# pnc3000-interface.net
KiCad netlist of a schematic drawn in EAGLE
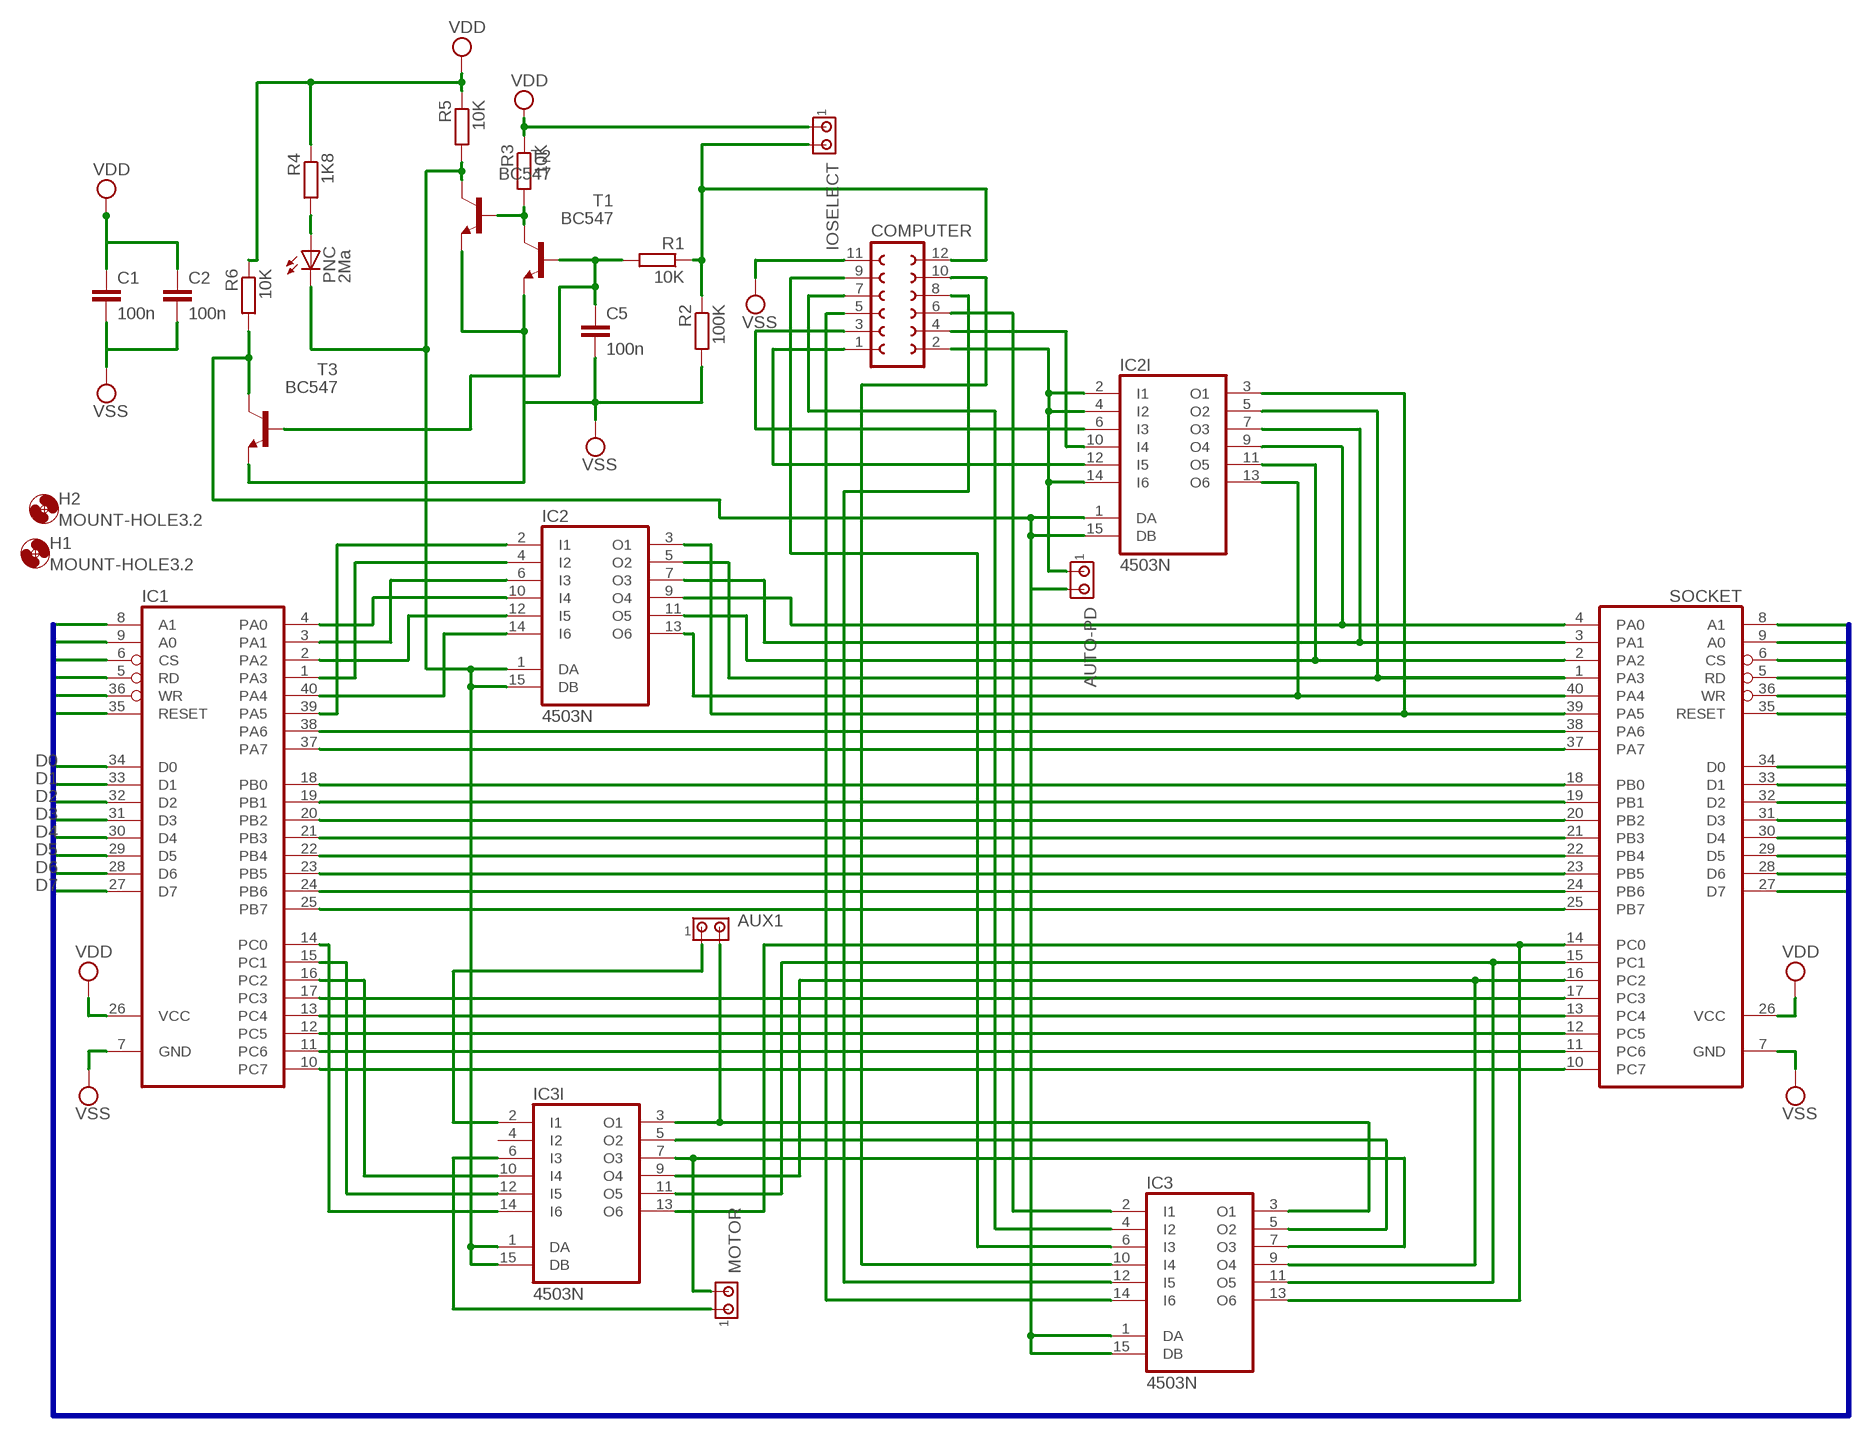
[diagram p0: schematic, sheet 1]

(export (version "E")
  (design (tool "Eeschema 10.0.6"))
  (components
    (comp (ref "AUTO-PD")
      (value "MTA02-100")
      (footprint "eagle-import:10X02MTA")
      (libsource (lib "eagle-import") (part "MTA02-100"))
    )
    (comp (ref "AUX1")
      (value "MTA02-100")
      (footprint "eagle-import:10X02MTA")
      (libsource (lib "eagle-import") (part "MTA02-100"))
    )
    (comp (ref "C1")
      (value "100n")
      (footprint "eagle-import:C050-024X044")
      (libsource (lib "eagle-import") (part "C-EU050-024X044"))
    )
    (comp (ref "C2")
      (value "100n")
      (footprint "eagle-import:C050-024X044")
      (libsource (lib "eagle-import") (part "C-EU050-024X044"))
    )
    (comp (ref "C5")
      (value "100n")
      (footprint "eagle-import:C050-024X044")
      (libsource (lib "eagle-import") (part "C-EU050-024X044"))
    )
    (comp (ref "COMPUTER")
      (value "FE06-2W")
      (footprint "eagle-import:FE06-2W")
      (libsource (lib "eagle-import") (part "FE06-2W"))
    )
    (comp (ref "H1")
      (value "MOUNT-HOLE3.2")
      (footprint "eagle-import:3,2")
      (libsource (lib "eagle-import") (part "MOUNT-HOLE3.2"))
    )
    (comp (ref "H2")
      (value "MOUNT-HOLE3.2")
      (footprint "eagle-import:3,2")
      (libsource (lib "eagle-import") (part "MOUNT-HOLE3.2"))
    )
    (comp (ref "IC1")
      (value "82C55A")
      (footprint "eagle-import:DIL40")
      (fields (field (name "MF") "INTERSIL") (field (name "MPN") "IP82C55AZ"))
      (libsource (lib "eagle-import") (part "82C55A"))
    )
    (comp (ref "IC2")
      (value "4503N")
      (footprint "eagle-import:DIL16")
      (libsource (lib "eagle-import") (part "4503N"))
    )
    (comp (ref "IC2I")
      (value "4503N")
      (footprint "eagle-import:DIL16")
      (libsource (lib "eagle-import") (part "4503N"))
    )
    (comp (ref "IC3")
      (value "4503N")
      (footprint "eagle-import:DIL16")
      (libsource (lib "eagle-import") (part "4503N"))
    )
    (comp (ref "IC3I")
      (value "4503N")
      (footprint "eagle-import:DIL16")
      (libsource (lib "eagle-import") (part "4503N"))
    )
    (comp (ref "IOSELECT")
      (value "MTA02-100")
      (footprint "eagle-import:10X02MTA")
      (libsource (lib "eagle-import") (part "MTA02-100"))
    )
    (comp (ref "MOTOR")
      (value "MTA02-100")
      (footprint "eagle-import:10X02MTA")
      (libsource (lib "eagle-import") (part "MTA02-100"))
    )
    (comp (ref "PNC")
      (value "2Ma")
      (footprint "eagle-import:LED5MM")
      (libsource (lib "eagle-import") (part "LED5MM"))
    )
    (comp (ref "R1")
      (value "10K")
      (footprint "eagle-import:0207_10")
      (libsource (lib "eagle-import") (part "R-EU_0207/10"))
    )
    (comp (ref "R2")
      (value "100K")
      (footprint "eagle-import:0207_10")
      (libsource (lib "eagle-import") (part "R-EU_0207/10"))
    )
    (comp (ref "R3")
      (value "10K")
      (footprint "eagle-import:0207_10")
      (libsource (lib "eagle-import") (part "R-EU_0207/10"))
    )
    (comp (ref "R4")
      (value "1K8")
      (footprint "eagle-import:0207_10")
      (libsource (lib "eagle-import") (part "R-EU_0207/10"))
    )
    (comp (ref "R5")
      (value "10K")
      (footprint "eagle-import:0207_10")
      (libsource (lib "eagle-import") (part "R-EU_0207/10"))
    )
    (comp (ref "R6")
      (value "10K")
      (footprint "eagle-import:0207_10")
      (libsource (lib "eagle-import") (part "R-EU_0207/10"))
    )
    (comp (ref "SOCKET")
      (value "82C55A")
      (footprint "eagle-import:DIL40")
      (fields (field (name "MF") "INTERSIL") (field (name "MPN") "IP82C55AZ"))
      (libsource (lib "eagle-import") (part "82C55A"))
    )
    (comp (ref "T1")
      (value "BC547")
      (footprint "eagle-import:TO92")
      (libsource (lib "eagle-import") (part "BC547"))
    )
    (comp (ref "T2")
      (value "BC547")
      (footprint "eagle-import:TO92")
      (libsource (lib "eagle-import") (part "BC547"))
    )
    (comp (ref "T3")
      (value "BC547")
      (footprint "eagle-import:TO92")
      (libsource (lib "eagle-import") (part "BC547"))
    )
  )
  (nets
    (net (code "1") (name "/A0") (class "Default")
      (node (ref "IC1") (pin "9") (pinfunction "A0_9") (pintype "input"))
      (node (ref "SOCKET") (pin "9") (pinfunction "A0_9") (pintype "input"))
    )
    (net (code "2") (name "/A1") (class "Default")
      (node (ref "IC1") (pin "8") (pinfunction "A1_8") (pintype "input"))
      (node (ref "SOCKET") (pin "8") (pinfunction "A1_8") (pintype "input"))
    )
    (net (code "3") (name "/CS") (class "Default")
      (node (ref "IC1") (pin "6") (pinfunction "CS_6") (pintype "input"))
      (node (ref "SOCKET") (pin "6") (pinfunction "CS_6") (pintype "input"))
    )
    (net (code "4") (name "/D0") (class "Default")
      (node (ref "IC1") (pin "34") (pinfunction "D0_34") (pintype "bidirectional"))
      (node (ref "SOCKET") (pin "34") (pinfunction "D0_34") (pintype "bidirectional"))
    )
    (net (code "5") (name "/D1") (class "Default")
      (node (ref "IC1") (pin "33") (pinfunction "D1_33") (pintype "bidirectional"))
      (node (ref "SOCKET") (pin "33") (pinfunction "D1_33") (pintype "bidirectional"))
    )
    (net (code "6") (name "/D2") (class "Default")
      (node (ref "IC1") (pin "32") (pinfunction "D2_32") (pintype "bidirectional"))
      (node (ref "SOCKET") (pin "32") (pinfunction "D2_32") (pintype "bidirectional"))
    )
    (net (code "7") (name "/D3") (class "Default")
      (node (ref "IC1") (pin "31") (pinfunction "D3_31") (pintype "bidirectional"))
      (node (ref "SOCKET") (pin "31") (pinfunction "D3_31") (pintype "bidirectional"))
    )
    (net (code "8") (name "/D4") (class "Default")
      (node (ref "IC1") (pin "30") (pinfunction "D4_30") (pintype "bidirectional"))
      (node (ref "SOCKET") (pin "30") (pinfunction "D4_30") (pintype "bidirectional"))
    )
    (net (code "9") (name "/D5") (class "Default")
      (node (ref "IC1") (pin "29") (pinfunction "D5_29") (pintype "bidirectional"))
      (node (ref "SOCKET") (pin "29") (pinfunction "D5_29") (pintype "bidirectional"))
    )
    (net (code "10") (name "/D6") (class "Default")
      (node (ref "IC1") (pin "28") (pinfunction "D6_28") (pintype "bidirectional"))
      (node (ref "SOCKET") (pin "28") (pinfunction "D6_28") (pintype "bidirectional"))
    )
    (net (code "11") (name "/D7") (class "Default")
      (node (ref "IC1") (pin "27") (pinfunction "D7_27") (pintype "bidirectional"))
      (node (ref "SOCKET") (pin "27") (pinfunction "D7_27") (pintype "bidirectional"))
    )
    (net (code "12") (name "/RD") (class "Default")
      (node (ref "IC1") (pin "5") (pinfunction "RD_5") (pintype "input"))
      (node (ref "SOCKET") (pin "5") (pinfunction "RD_5") (pintype "input"))
    )
    (net (code "13") (name "/RESET") (class "Default")
      (node (ref "IC1") (pin "35") (pinfunction "RESET_35") (pintype "input"))
      (node (ref "SOCKET") (pin "35") (pinfunction "RESET_35") (pintype "input"))
    )
    (net (code "14") (name "/WR") (class "Default")
      (node (ref "IC1") (pin "36") (pinfunction "WR_36") (pintype "input"))
      (node (ref "SOCKET") (pin "36") (pinfunction "WR_36") (pintype "input"))
    )
    (net (code "15") (name "Net-(COMPUTER-Pad12)") (class "Default")
      (node (ref "COMPUTER") (pin "12") (pinfunction "12_12") (pintype "passive"))
      (node (ref "IOSELECT") (pin "2") (pinfunction "2_2") (pintype "passive"))
      (node (ref "R1") (pin "1") (pinfunction "1_1") (pintype "passive"))
      (node (ref "R2") (pin "1") (pinfunction "1_1") (pintype "passive"))
    )
    (net (code "16") (name "Net-(IC1-PA0)") (class "Default")
      (node (ref "IC1") (pin "4") (pinfunction "PA0_4") (pintype "bidirectional"))
      (node (ref "IC2") (pin "10") (pinfunction "I4_10") (pintype "input"))
    )
    (net (code "17") (name "Net-(IC1-PA1)") (class "Default")
      (node (ref "IC1") (pin "3") (pinfunction "PA1_3") (pintype "bidirectional"))
      (node (ref "IC2") (pin "6") (pinfunction "I3_6") (pintype "input"))
    )
    (net (code "18") (name "Net-(IC1-PA2)") (class "Default")
      (node (ref "IC1") (pin "2") (pinfunction "PA2_2") (pintype "bidirectional"))
      (node (ref "IC2") (pin "12") (pinfunction "I5_12") (pintype "input"))
    )
    (net (code "19") (name "Net-(IC1-PA3)") (class "Default")
      (node (ref "IC1") (pin "1") (pinfunction "PA3_1") (pintype "bidirectional"))
      (node (ref "IC2") (pin "4") (pinfunction "I2_4") (pintype "input"))
    )
    (net (code "20") (name "Net-(IC1-PA4)") (class "Default")
      (node (ref "IC1") (pin "40") (pinfunction "PA4_40") (pintype "bidirectional"))
      (node (ref "IC2") (pin "14") (pinfunction "I6_14") (pintype "input"))
    )
    (net (code "21") (name "Net-(IC1-PA5)") (class "Default")
      (node (ref "IC1") (pin "39") (pinfunction "PA5_39") (pintype "bidirectional"))
      (node (ref "IC2") (pin "2") (pinfunction "I1_2") (pintype "input"))
    )
    (net (code "22") (name "Net-(IC1-PA6)") (class "Default")
      (node (ref "IC1") (pin "38") (pinfunction "PA6_38") (pintype "bidirectional"))
      (node (ref "SOCKET") (pin "38") (pinfunction "PA6_38") (pintype "bidirectional"))
    )
    (net (code "23") (name "Net-(IC1-PA7)") (class "Default")
      (node (ref "IC1") (pin "37") (pinfunction "PA7_37") (pintype "bidirectional"))
      (node (ref "SOCKET") (pin "37") (pinfunction "PA7_37") (pintype "bidirectional"))
    )
    (net (code "24") (name "Net-(IC1-PB0)") (class "Default")
      (node (ref "IC1") (pin "18") (pinfunction "PB0_18") (pintype "bidirectional"))
      (node (ref "SOCKET") (pin "18") (pinfunction "PB0_18") (pintype "bidirectional"))
    )
    (net (code "25") (name "Net-(IC1-PB1)") (class "Default")
      (node (ref "IC1") (pin "19") (pinfunction "PB1_19") (pintype "bidirectional"))
      (node (ref "SOCKET") (pin "19") (pinfunction "PB1_19") (pintype "bidirectional"))
    )
    (net (code "26") (name "Net-(IC1-PB2)") (class "Default")
      (node (ref "IC1") (pin "20") (pinfunction "PB2_20") (pintype "bidirectional"))
      (node (ref "SOCKET") (pin "20") (pinfunction "PB2_20") (pintype "bidirectional"))
    )
    (net (code "27") (name "Net-(IC1-PB3)") (class "Default")
      (node (ref "IC1") (pin "21") (pinfunction "PB3_21") (pintype "bidirectional"))
      (node (ref "SOCKET") (pin "21") (pinfunction "PB3_21") (pintype "bidirectional"))
    )
    (net (code "28") (name "Net-(IC1-PB4)") (class "Default")
      (node (ref "IC1") (pin "22") (pinfunction "PB4_22") (pintype "bidirectional"))
      (node (ref "SOCKET") (pin "22") (pinfunction "PB4_22") (pintype "bidirectional"))
    )
    (net (code "29") (name "Net-(IC1-PB5)") (class "Default")
      (node (ref "IC1") (pin "23") (pinfunction "PB5_23") (pintype "bidirectional"))
      (node (ref "SOCKET") (pin "23") (pinfunction "PB5_23") (pintype "bidirectional"))
    )
    (net (code "30") (name "Net-(IC1-PB6)") (class "Default")
      (node (ref "IC1") (pin "24") (pinfunction "PB6_24") (pintype "bidirectional"))
      (node (ref "SOCKET") (pin "24") (pinfunction "PB6_24") (pintype "bidirectional"))
    )
    (net (code "31") (name "Net-(IC1-PB7)") (class "Default")
      (node (ref "IC1") (pin "25") (pinfunction "PB7_25") (pintype "bidirectional"))
      (node (ref "SOCKET") (pin "25") (pinfunction "PB7_25") (pintype "bidirectional"))
    )
    (net (code "32") (name "Net-(IC1-PC0)") (class "Default")
      (node (ref "IC1") (pin "14") (pinfunction "PC0_14") (pintype "bidirectional"))
      (node (ref "IC3I") (pin "14") (pinfunction "I6_14") (pintype "input"))
    )
    (net (code "33") (name "Net-(IC1-PC1)") (class "Default")
      (node (ref "IC1") (pin "15") (pinfunction "PC1_15") (pintype "bidirectional"))
      (node (ref "IC3I") (pin "12") (pinfunction "I5_12") (pintype "input"))
    )
    (net (code "34") (name "Net-(IC1-PC2)") (class "Default")
      (node (ref "IC1") (pin "16") (pinfunction "PC2_16") (pintype "bidirectional"))
      (node (ref "IC3I") (pin "10") (pinfunction "I4_10") (pintype "input"))
    )
    (net (code "35") (name "Net-(IC1-PC3)") (class "Default")
      (node (ref "IC1") (pin "17") (pinfunction "PC3_17") (pintype "bidirectional"))
      (node (ref "SOCKET") (pin "17") (pinfunction "PC3_17") (pintype "bidirectional"))
    )
    (net (code "36") (name "Net-(IC1-PC4)") (class "Default")
      (node (ref "IC1") (pin "13") (pinfunction "PC4_13") (pintype "bidirectional"))
      (node (ref "SOCKET") (pin "13") (pinfunction "PC4_13") (pintype "bidirectional"))
    )
    (net (code "37") (name "Net-(IC1-PC5)") (class "Default")
      (node (ref "IC1") (pin "12") (pinfunction "PC5_12") (pintype "bidirectional"))
      (node (ref "SOCKET") (pin "12") (pinfunction "PC5_12") (pintype "bidirectional"))
    )
    (net (code "38") (name "Net-(IC1-PC6)") (class "Default")
      (node (ref "IC1") (pin "11") (pinfunction "PC6_11") (pintype "bidirectional"))
      (node (ref "SOCKET") (pin "11") (pinfunction "PC6_11") (pintype "bidirectional"))
    )
    (net (code "39") (name "Net-(IC1-PC7)") (class "Default")
      (node (ref "IC1") (pin "10") (pinfunction "PC7_10") (pintype "bidirectional"))
      (node (ref "SOCKET") (pin "10") (pinfunction "PC7_10") (pintype "bidirectional"))
    )
    (net (code "40") (name "Net-(IC2A-DA)") (class "Default")
      (node (ref "IC2") (pin "1") (pinfunction "DA_1") (pintype "input"))
      (node (ref "IC2") (pin "15") (pinfunction "DB_15") (pintype "input"))
      (node (ref "IC3I") (pin "1") (pinfunction "DA_1") (pintype "input"))
      (node (ref "IC3I") (pin "15") (pinfunction "DB_15") (pintype "input"))
      (node (ref "PNC") (pin "K") (pinfunction "C_K") (pintype "passive"))
      (node (ref "R5") (pin "2") (pinfunction "2_2") (pintype "passive"))
      (node (ref "T2") (pin "3") (pinfunction "C_3") (pintype "passive"))
    )
    (net (code "41") (name "Net-(IC2A-O1)") (class "Default")
      (node (ref "IC2") (pin "3") (pinfunction "O1_3") (pintype "output"))
      (node (ref "IC2I") (pin "3") (pinfunction "O1_3") (pintype "output"))
      (node (ref "SOCKET") (pin "39") (pinfunction "PA5_39") (pintype "bidirectional"))
    )
    (net (code "42") (name "Net-(IC2A-O2)") (class "Default")
      (node (ref "IC2") (pin "5") (pinfunction "O2_5") (pintype "output"))
      (node (ref "IC2I") (pin "5") (pinfunction "O2_5") (pintype "output"))
      (node (ref "SOCKET") (pin "1") (pinfunction "PA3_1") (pintype "bidirectional"))
    )
    (net (code "43") (name "Net-(IC2A-O3)") (class "Default")
      (node (ref "IC2") (pin "7") (pinfunction "O3_7") (pintype "output"))
      (node (ref "IC2I") (pin "7") (pinfunction "O3_7") (pintype "output"))
      (node (ref "SOCKET") (pin "3") (pinfunction "PA1_3") (pintype "bidirectional"))
    )
    (net (code "44") (name "Net-(IC2A-O4)") (class "Default")
      (node (ref "IC2") (pin "9") (pinfunction "O4_9") (pintype "output"))
      (node (ref "IC2I") (pin "9") (pinfunction "O4_9") (pintype "output"))
      (node (ref "SOCKET") (pin "4") (pinfunction "PA0_4") (pintype "bidirectional"))
    )
    (net (code "45") (name "Net-(IC2A-O5)") (class "Default")
      (node (ref "IC2") (pin "11") (pinfunction "O5_11") (pintype "output"))
      (node (ref "IC2I") (pin "11") (pinfunction "O5_11") (pintype "output"))
      (node (ref "SOCKET") (pin "2") (pinfunction "PA2_2") (pintype "bidirectional"))
    )
    (net (code "46") (name "Net-(IC2A-O6)") (class "Default")
      (node (ref "IC2") (pin "13") (pinfunction "O6_13") (pintype "output"))
      (node (ref "IC2I") (pin "13") (pinfunction "O6_13") (pintype "output"))
      (node (ref "SOCKET") (pin "40") (pinfunction "PA4_40") (pintype "bidirectional"))
    )
    (net (code "47") (name "Net-(IC2IA-DA)") (class "Default")
      (node (ref "AUTO-PD") (pin "2") (pinfunction "2_2") (pintype "passive"))
      (node (ref "IC2I") (pin "1") (pinfunction "DA_1") (pintype "input"))
      (node (ref "IC2I") (pin "15") (pinfunction "DB_15") (pintype "input"))
      (node (ref "IC3") (pin "1") (pinfunction "DA_1") (pintype "input"))
      (node (ref "IC3") (pin "15") (pinfunction "DB_15") (pintype "input"))
      (node (ref "R6") (pin "2") (pinfunction "2_2") (pintype "passive"))
      (node (ref "T3") (pin "3") (pinfunction "C_3") (pintype "passive"))
    )
    (net (code "48") (name "Net-(IC2IA-I1)") (class "Default")
      (node (ref "AUTO-PD") (pin "1") (pinfunction "1_1") (pintype "passive"))
      (node (ref "COMPUTER") (pin "2") (pinfunction "2_2") (pintype "passive"))
      (node (ref "IC2I") (pin "14") (pinfunction "I6_14") (pintype "input"))
      (node (ref "IC2I") (pin "2") (pinfunction "I1_2") (pintype "input"))
      (node (ref "IC2I") (pin "4") (pinfunction "I2_4") (pintype "input"))
    )
    (net (code "49") (name "Net-(IC2IA-I3)") (class "Default")
      (node (ref "COMPUTER") (pin "3") (pinfunction "3_3") (pintype "passive"))
      (node (ref "IC2I") (pin "6") (pinfunction "I3_6") (pintype "input"))
    )
    (net (code "50") (name "Net-(IC2IA-I4)") (class "Default")
      (node (ref "COMPUTER") (pin "4") (pinfunction "4_4") (pintype "passive"))
      (node (ref "IC2I") (pin "10") (pinfunction "I4_10") (pintype "input"))
    )
    (net (code "51") (name "Net-(IC2IA-I5)") (class "Default")
      (node (ref "COMPUTER") (pin "1") (pinfunction "1_1") (pintype "passive"))
      (node (ref "IC2I") (pin "12") (pinfunction "I5_12") (pintype "input"))
    )
    (net (code "52") (name "Net-(IC3A-I1)") (class "Default")
      (node (ref "COMPUTER") (pin "6") (pinfunction "6_6") (pintype "passive"))
      (node (ref "IC3") (pin "2") (pinfunction "I1_2") (pintype "input"))
    )
    (net (code "53") (name "Net-(IC3A-I2)") (class "Default")
      (node (ref "COMPUTER") (pin "7") (pinfunction "7_7") (pintype "passive"))
      (node (ref "IC3") (pin "4") (pinfunction "I2_4") (pintype "input"))
    )
    (net (code "54") (name "Net-(IC3A-I3)") (class "Default")
      (node (ref "COMPUTER") (pin "9") (pinfunction "9_9") (pintype "passive"))
      (node (ref "IC3") (pin "6") (pinfunction "I3_6") (pintype "input"))
    )
    (net (code "55") (name "Net-(IC3A-I4)") (class "Default")
      (node (ref "COMPUTER") (pin "10") (pinfunction "10_10") (pintype "passive"))
      (node (ref "IC3") (pin "10") (pinfunction "I4_10") (pintype "input"))
    )
    (net (code "56") (name "Net-(IC3A-I5)") (class "Default")
      (node (ref "COMPUTER") (pin "8") (pinfunction "8_8") (pintype "passive"))
      (node (ref "IC3") (pin "12") (pinfunction "I5_12") (pintype "input"))
    )
    (net (code "57") (name "Net-(IC3A-I6)") (class "Default")
      (node (ref "COMPUTER") (pin "5") (pinfunction "5_5") (pintype "passive"))
      (node (ref "IC3") (pin "14") (pinfunction "I6_14") (pintype "input"))
    )
    (net (code "58") (name "Net-(IC3A-O1)") (class "Default")
      (node (ref "AUX1") (pin "2") (pinfunction "2_2") (pintype "passive"))
      (node (ref "IC3") (pin "3") (pinfunction "O1_3") (pintype "output"))
      (node (ref "IC3I") (pin "3") (pinfunction "O1_3") (pintype "output"))
    )
    (net (code "59") (name "Net-(IC3A-O2)") (class "Default")
      (node (ref "IC3") (pin "5") (pinfunction "O2_5") (pintype "output"))
      (node (ref "IC3I") (pin "5") (pinfunction "O2_5") (pintype "output"))
    )
    (net (code "60") (name "Net-(IC3A-O3)") (class "Default")
      (node (ref "IC3") (pin "7") (pinfunction "O3_7") (pintype "output"))
      (node (ref "IC3I") (pin "7") (pinfunction "O3_7") (pintype "output"))
      (node (ref "MOTOR") (pin "2") (pinfunction "2_2") (pintype "passive"))
    )
    (net (code "61") (name "Net-(IC3A-O4)") (class "Default")
      (node (ref "IC3") (pin "9") (pinfunction "O4_9") (pintype "output"))
      (node (ref "IC3I") (pin "9") (pinfunction "O4_9") (pintype "output"))
      (node (ref "SOCKET") (pin "16") (pinfunction "PC2_16") (pintype "bidirectional"))
    )
    (net (code "62") (name "Net-(IC3A-O5)") (class "Default")
      (node (ref "IC3") (pin "11") (pinfunction "O5_11") (pintype "output"))
      (node (ref "IC3I") (pin "11") (pinfunction "O5_11") (pintype "output"))
      (node (ref "SOCKET") (pin "15") (pinfunction "PC1_15") (pintype "bidirectional"))
    )
    (net (code "63") (name "Net-(IC3A-O6)") (class "Default")
      (node (ref "IC3") (pin "13") (pinfunction "O6_13") (pintype "output"))
      (node (ref "IC3I") (pin "13") (pinfunction "O6_13") (pintype "output"))
      (node (ref "SOCKET") (pin "14") (pinfunction "PC0_14") (pintype "bidirectional"))
    )
    (net (code "64") (name "Net-(IC3IA-I1)") (class "Default")
      (node (ref "AUX1") (pin "1") (pinfunction "1_1") (pintype "passive"))
      (node (ref "IC3I") (pin "2") (pinfunction "I1_2") (pintype "input"))
    )
    (net (code "65") (name "Net-(IC3IA-I3)") (class "Default")
      (node (ref "IC3I") (pin "6") (pinfunction "I3_6") (pintype "input"))
      (node (ref "MOTOR") (pin "1") (pinfunction "1_1") (pintype "passive"))
    )
    (net (code "66") (name "Net-(PNC-PadA)") (class "Default")
      (node (ref "PNC") (pin "A") (pinfunction "A_A") (pintype "passive"))
      (node (ref "R4") (pin "2") (pinfunction "2_2") (pintype "passive"))
    )
    (net (code "67") (name "Net-(T1-B)") (class "Default")
      (node (ref "C5") (pin "1") (pinfunction "1_1") (pintype "passive"))
      (node (ref "R1") (pin "2") (pinfunction "2_2") (pintype "passive"))
      (node (ref "T1") (pin "2") (pinfunction "B_2") (pintype "passive"))
      (node (ref "T3") (pin "2") (pinfunction "B_2") (pintype "passive"))
    )
    (net (code "68") (name "Net-(T1-C)") (class "Default")
      (node (ref "R3") (pin "2") (pinfunction "2_2") (pintype "passive"))
      (node (ref "T1") (pin "3") (pinfunction "C_3") (pintype "passive"))
      (node (ref "T2") (pin "2") (pinfunction "B_2") (pintype "passive"))
    )
    (net (code "69") (name "VDD") (class "Default")
      (node (ref "C1") (pin "1") (pinfunction "1_1") (pintype "passive"))
      (node (ref "C2") (pin "1") (pinfunction "1_1") (pintype "passive"))
      (node (ref "IC1") (pin "26") (pinfunction "VCC_26") (pintype "power_in"))
      (node (ref "IOSELECT") (pin "1") (pinfunction "1_1") (pintype "passive"))
      (node (ref "R3") (pin "1") (pinfunction "1_1") (pintype "passive"))
      (node (ref "R4") (pin "1") (pinfunction "1_1") (pintype "passive"))
      (node (ref "R5") (pin "1") (pinfunction "1_1") (pintype "passive"))
      (node (ref "R6") (pin "1") (pinfunction "1_1") (pintype "passive"))
      (node (ref "SOCKET") (pin "26") (pinfunction "VCC_26") (pintype "power_in"))
    )
    (net (code "70") (name "VSS") (class "Default")
      (node (ref "C1") (pin "2") (pinfunction "2_2") (pintype "passive"))
      (node (ref "C2") (pin "2") (pinfunction "2_2") (pintype "passive"))
      (node (ref "C5") (pin "2") (pinfunction "2_2") (pintype "passive"))
      (node (ref "COMPUTER") (pin "11") (pinfunction "11_11") (pintype "passive"))
      (node (ref "IC1") (pin "7") (pinfunction "GND_7") (pintype "power_in"))
      (node (ref "R2") (pin "2") (pinfunction "2_2") (pintype "passive"))
      (node (ref "SOCKET") (pin "7") (pinfunction "GND_7") (pintype "power_in"))
      (node (ref "T1") (pin "1") (pinfunction "E_1") (pintype "passive"))
      (node (ref "T2") (pin "1") (pinfunction "E_1") (pintype "passive"))
      (node (ref "T3") (pin "1") (pinfunction "E_1") (pintype "passive"))
    )
    (net (code "71") (name "unconnected-(IC3IA-I2-Pad4)") (class "Default")
      (node (ref "IC3I") (pin "4") (pinfunction "I2_4") (pintype "input"))
    )
  )
)
